# MSB.net
KiCad netlist of a schematic drawn in Altium Designer
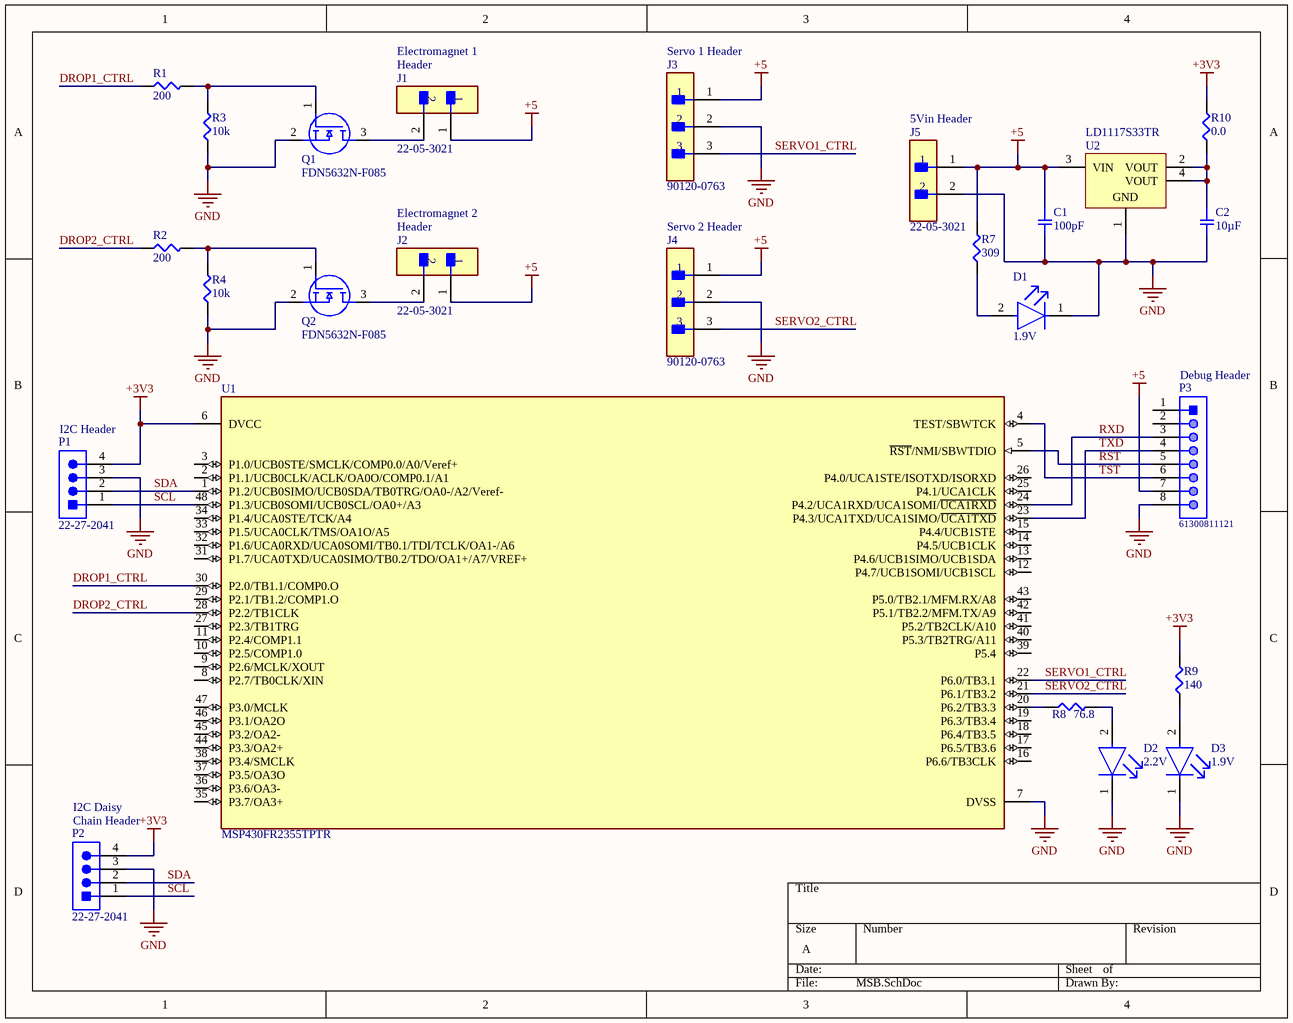
[diagram p0: MSB.SchDoc]

(export (version "E")
  (design (tool "Eeschema 10.0.6"))
  (components
    (comp (ref "C1")
      (value "100pF")
      (footprint "SMD-0805C")
      (description "CAP CER 100PF 50V NP0 0805")
      (fields
        (field (name "MANUFACTURER") "Murata Electronics North America")
        (field (name "TOLERANCE") "±5%")
      )
      (libsource (lib "capacitor_murata_0805") (part "GQM2195C1H101JB01D"))
    )
    (comp (ref "C2")
      (value "10µF")
      (footprint "SMD-0805C")
      (description "CAP CER 10UF 10V X7R 0805")
      (fields
        (field (name "MANUFACTURER") "Murata Electronics North America")
        (field (name "TOLERANCE") "±10%")
      )
      (libsource (lib "capacitor_murata_0805") (part "GCJ21BR71A106KE01L"))
    )
    (comp (ref "D1")
      (value "1.9V")
      (footprint "FP-150080SS75000-MFG")
      (description "LED RED CLEAR 0805 SMD, 150080SS75000")
      (fields
        (field (name "MANUFACTURER") "Wurth Elektronik")
        (field (name "MANUFACTURER PART NUMBER") "150080SS75000")
      )
      (libsource (lib "Altium Content Vault") (part "8706943c75ba83719d021d2fdc84c58"))
    )
    (comp (ref "D2")
      (value "2.2V")
      (footprint "FP-LTST-C171GKT-MFG")
      (description "LED GREEN CLEAR CHIP SMD, LTST-C171GKT")
      (fields (field (name "MANUFACTURER") "Vishay") (field (name "MANUFACTURER PART NUMBER") "LTST-C171GKT"))
      (libsource (lib "Altium Content Vault") (part "8706943c75ba83719d021d2fdc84c58"))
    )
    (comp (ref "D3")
      (value "1.9V")
      (footprint "FP-150080SS75000-MFG")
      (description "LED RED CLEAR 0805 SMD, 150080SS75000")
      (fields
        (field (name "MANUFACTURER") "Wurth Elektronik")
        (field (name "MANUFACTURER PART NUMBER") "150080SS75000")
      )
      (libsource (lib "Altium Content Vault") (part "8706943c75ba83719d021d2fdc84c58"))
    )
    (comp (ref "J1")
      (value "22-05-3021")
      (footprint "FP-22-05-3021-MFG")
      (description "CONN HEADER R/A 2POS 2.54MM")
      (fields (field (name "MANUFACTURER") "Molex"))
      (libsource (lib "Altium Content Vault") (part "3bc925449376181038e59eaffc5286c"))
    )
    (comp (ref "J2")
      (value "22-05-3021")
      (footprint "FP-22-05-3021-MFG")
      (description "CONN HEADER R/A 2POS 2.54MM")
      (fields (field (name "MANUFACTURER") "Molex"))
      (libsource (lib "Altium Content Vault") (part "3bc925449376181038e59eaffc5286c"))
    )
    (comp (ref "J3")
      (value "90120-0763")
      (footprint "FP-90120-0763-MFG")
      (description "CONN HEADER VERT 3POS 2.54MM")
      (fields (field (name "MANUFACTURER") "Molex"))
      (libsource (lib "Altium Content Vault") (part "0d3f023dd272f625e17a2be33dea85f"))
    )
    (comp (ref "J4")
      (value "90120-0763")
      (footprint "FP-90120-0763-MFG")
      (description "CONN HEADER VERT 3POS 2.54MM")
      (fields (field (name "MANUFACTURER") "Molex"))
      (libsource (lib "Altium Content Vault") (part "0d3f023dd272f625e17a2be33dea85f"))
    )
    (comp (ref "J5")
      (value "22-05-3021")
      (footprint "FP-22-05-3021-MFG")
      (description "CONN HEADER R/A 2POS 2.54MM")
      (fields (field (name "MANUFACTURER") "Molex"))
      (libsource (lib "") (part "3bc925449376181038e59eaffc5286c_1"))
    )
    (comp (ref "P1")
      (value "22-27-2041")
      (footprint "MOLX-22-27-2041_V")
      (description "Male Header, Pitch 2.54 mm, 1 x 4 Position, Height 11.7 mm, Tail Length 3.56 mm, RoHS, Bulk")
      (fields (field (name "MANUFACTURER") "Molex"))
      (libsource (lib "Altium Content Vault") (part "CN-1P-M-R4"))
    )
    (comp (ref "P2")
      (value "22-27-2041")
      (footprint "MOLX-22-27-2041_V")
      (description "Male Header, Pitch 2.54 mm, 1 x 4 Position, Height 11.7 mm, Tail Length 3.56 mm, RoHS, Bulk")
      (fields (field (name "MANUFACTURER") "Molex"))
      (libsource (lib "Altium Content Vault") (part "CN-1P-M-R4"))
    )
    (comp (ref "P3")
      (value "61300811121")
      (footprint "61300811121")
      (description "THT Vertical Pin Header WR-PHD, Pitch 2.54 mm, Single Row, 8 pins")
      (fields (field (name "MANUFACTURER") "Wurth Elektronik"))
      (libsource (lib "Altium Content Vault") (part "WE-CN-1P-M-R8"))
    )
    (comp (ref "Q1")
      (value "FDN5632N-F085")
      (footprint "SOT95P237X122-3N")
      (description "MOSFET Trans MOS N-Ch 60V 1.7A")
      (fields (field (name "MANUFACTURER") "Onsemi"))
      (libsource (lib "FDN5632N-F085") (part "FDN5632N-F085"))
    )
    (comp (ref "Q2")
      (value "FDN5632N-F085")
      (footprint "SOT95P237X122-3N")
      (description "MOSFET Trans MOS N-Ch 60V 1.7A")
      (fields (field (name "MANUFACTURER") "Onsemi"))
      (libsource (lib "FDN5632N-F085") (part "FDN5632N-F085"))
    )
    (comp (ref "R1")
      (value "200")
      (footprint "SMD-0805-RES")
      (description "RES SMD 200 OHM 0.5% 1/4W 0805")
      (fields
        (field (name "MANUFACTURER") "Panasonic Electronic Components")
        (field (name "TOLERANCE") "±0.5%")
      )
      (libsource (lib "Panasonic_resistor_0805") (part "ERJ-PB6D2000V"))
    )
    (comp (ref "R2")
      (value "200")
      (footprint "SMD-0805-RES")
      (description "RES SMD 200 OHM 0.5% 1/4W 0805")
      (fields
        (field (name "MANUFACTURER") "Panasonic Electronic Components")
        (field (name "TOLERANCE") "±0.5%")
      )
      (libsource (lib "Panasonic_resistor_0805") (part "ERJ-PB6D2000V"))
    )
    (comp (ref "R3")
      (value "10k")
      (footprint "SMD-0805-RES")
      (description "RES SMD 10K OHM 1% 1/8W 0805")
      (fields
        (field (name "MANUFACTURER") "Panasonic Electronic Components")
        (field (name "TOLERANCE") "±1%")
      )
      (libsource (lib "Panasonic_resistor_0805") (part "ERJ-6ENF1002V"))
    )
    (comp (ref "R4")
      (value "10k")
      (footprint "SMD-0805-RES")
      (description "RES SMD 10K OHM 1% 1/8W 0805")
      (fields
        (field (name "MANUFACTURER") "Panasonic Electronic Components")
        (field (name "TOLERANCE") "±1%")
      )
      (libsource (lib "Panasonic_resistor_0805") (part "ERJ-6ENF1002V"))
    )
    (comp (ref "R7")
      (value "309")
      (footprint "SMD-0805-RES")
      (description "RES SMD 309 OHM 1% 1/8W 0805")
      (fields
        (field (name "MANUFACTURER") "Panasonic Electronic Components")
        (field (name "TOLERANCE") "±1%")
      )
      (libsource (lib "Panasonic_resistor_0805") (part "ERJ-6ENF3090V"))
    )
    (comp (ref "R8")
      (value "76.8")
      (footprint "SMD-0805-RES")
      (description "RES SMD 76.8 OHM 1% 1/8W 0805")
      (fields
        (field (name "MANUFACTURER") "Panasonic Electronic Components")
        (field (name "TOLERANCE") "±1%")
      )
      (libsource (lib "Panasonic_resistor_0805") (part "ERJ-6ENF76R8V"))
    )
    (comp (ref "R9")
      (value "140")
      (footprint "SMD-0805-RES")
      (description "RES SMD 140 OHM 1% 1/8W 0805")
      (fields
        (field (name "MANUFACTURER") "Panasonic Electronic Components")
        (field (name "TOLERANCE") "±1%")
      )
      (libsource (lib "Panasonic_resistor_0805") (part "ERJ-6ENF1400V"))
    )
    (comp (ref "R10")
      (value "0.0")
      (footprint "SMD-0805-RES")
      (description "RES SMD 0.0 OHM JUMPER 1/8W 0805")
      (fields
        (field (name "MANUFACTURER") "Panasonic Electronic Components")
        (field (name "TOLERANCE") "Jumper")
      )
      (libsource (lib "Panasonic_resistor_0805") (part "ERJ-6GEY0R00V"))
    )
    (comp (ref "U1")
      (value "MSP430FR2355TPTR")
      (footprint "FP-PT0048A-MFG")
      (description "IC MCU 16BIT 32KB FRAM 48LQFP")
      (fields (field (name "MANUFACTURER") "Texas Instruments"))
      (libsource (lib "Altium Content Vault") (part "bd983ca6877cdd146f198514b3acb3b"))
    )
    (comp (ref "U2")
      (value "LD1117S33TR")
      (footprint "SOT-223_L")
      (description "Fixed Low Drop Positive Voltage Regulator, 3.3V, 4-Pin SOT-223, Tape and Reel")
      (fields (field (name "MANUFACTURER") "Onsemi"))
      (libsource (lib "Altium Content Vault") (part "PM-REG-LD1117-SOT4"))
    )
  )
  (nets
    (net (code "1") (name "+3V3") (class "Default")
      (node (ref "P1") (pin "4") (pinfunction "4_4") (pintype "passive"))
      (node (ref "P2") (pin "4") (pinfunction "4_4") (pintype "passive"))
      (node (ref "R10") (pin "2") (pinfunction "2_2") (pintype "passive"))
      (node (ref "R9") (pin "2") (pinfunction "2_2") (pintype "passive"))
      (node (ref "U1") (pin "6") (pinfunction "DVCC_6") (pintype "power_in"))
    )
    (net (code "2") (name "+5") (class "Default")
      (node (ref "C1") (pin "1") (pinfunction "1_1") (pintype "passive"))
      (node (ref "J1") (pin "1") (pinfunction "1_1") (pintype "passive"))
      (node (ref "J2") (pin "1") (pinfunction "1_1") (pintype "passive"))
      (node (ref "J3") (pin "1") (pinfunction "1_1") (pintype "passive"))
      (node (ref "J4") (pin "1") (pinfunction "1_1") (pintype "passive"))
      (node (ref "J5") (pin "1") (pinfunction "1_1") (pintype "passive"))
      (node (ref "P3") (pin "7") (pinfunction "7_7") (pintype "passive"))
      (node (ref "R7") (pin "2") (pinfunction "2_2") (pintype "passive"))
      (node (ref "U2") (pin "3") (pinfunction "VIN_3") (pintype "power_in"))
    )
    (net (code "3") (name "/DROP1_CTRL") (class "Default")
      (node (ref "R1") (pin "1") (pinfunction "1_1") (pintype "passive"))
      (node (ref "U1") (pin "30") (pinfunction "P2.0/TB1.1/COMP0.O_30") (pintype "bidirectional"))
    )
    (net (code "4") (name "/DROP2_CTRL") (class "Default")
      (node (ref "R2") (pin "1") (pinfunction "1_1") (pintype "passive"))
      (node (ref "U1") (pin "28") (pinfunction "P2.2/TB1CLK_28") (pintype "bidirectional"))
    )
    (net (code "5") (name "/RST") (class "Default")
      (node (ref "P3") (pin "5") (pinfunction "5_5") (pintype "passive"))
      (node (ref "U1") (pin "5") (pinfunction "~{RST}/NMI/SBWTDIO_5") (pintype "input"))
    )
    (net (code "6") (name "/RXD") (class "Default")
      (node (ref "P3") (pin "3") (pinfunction "3_3") (pintype "passive"))
      (node (ref "U1") (pin "24") (pinfunction "P4.2/UCA1RXD/UCA1SOMI/~{UCA1RXD}_24") (pintype "bidirectional"))
    )
    (net (code "7") (name "/SCL") (class "Default")
      (node (ref "P1") (pin "1") (pinfunction "1_1") (pintype "passive"))
      (node (ref "P2") (pin "1") (pinfunction "1_1") (pintype "passive"))
      (node (ref "U1") (pin "48") (pinfunction "P1.3/UCB0SOMI/UCB0SCL/OA0+/A3_48") (pintype "bidirectional"))
    )
    (net (code "8") (name "/SDA") (class "Default")
      (node (ref "P1") (pin "2") (pinfunction "2_2") (pintype "passive"))
      (node (ref "P2") (pin "2") (pinfunction "2_2") (pintype "passive"))
      (node (ref "U1") (pin "1") (pinfunction "P1.2/UCB0SIMO/UCB0SDA/TB0TRG/OA0-/A2/Veref-_1") (pintype "bidirectional"))
    )
    (net (code "9") (name "/SERVO1_CTRL") (class "Default")
      (node (ref "J3") (pin "3") (pinfunction "3_3") (pintype "passive"))
      (node (ref "U1") (pin "22") (pinfunction "P6.0/TB3.1_22") (pintype "bidirectional"))
    )
    (net (code "10") (name "/SERVO2_CTRL") (class "Default")
      (node (ref "J4") (pin "3") (pinfunction "3_3") (pintype "passive"))
      (node (ref "U1") (pin "21") (pinfunction "P6.1/TB3.2_21") (pintype "bidirectional"))
    )
    (net (code "11") (name "/TST") (class "Default")
      (node (ref "P3") (pin "6") (pinfunction "6_6") (pintype "passive"))
      (node (ref "U1") (pin "4") (pinfunction "TEST/SBWTCK_4") (pintype "bidirectional"))
    )
    (net (code "12") (name "/TXD") (class "Default")
      (node (ref "P3") (pin "4") (pinfunction "4_4") (pintype "passive"))
      (node (ref "U1") (pin "23") (pinfunction "P4.3/UCA1TXD/UCA1SIMO/~{UCA1TXD}_23") (pintype "bidirectional"))
    )
    (net (code "13") (name "GND") (class "Default")
      (node (ref "C1") (pin "2") (pinfunction "2_2") (pintype "passive"))
      (node (ref "C2") (pin "2") (pinfunction "2_2") (pintype "passive"))
      (node (ref "D1") (pin "1") (pinfunction "C_1") (pintype "passive"))
      (node (ref "D2") (pin "1") (pinfunction "C_1") (pintype "passive"))
      (node (ref "D3") (pin "1") (pinfunction "C_1") (pintype "passive"))
      (node (ref "J3") (pin "2") (pinfunction "2_2") (pintype "passive"))
      (node (ref "J4") (pin "2") (pinfunction "2_2") (pintype "passive"))
      (node (ref "J5") (pin "2") (pinfunction "2_2") (pintype "passive"))
      (node (ref "P1") (pin "3") (pinfunction "3_3") (pintype "passive"))
      (node (ref "P2") (pin "3") (pinfunction "3_3") (pintype "passive"))
      (node (ref "P3") (pin "8") (pinfunction "8_8") (pintype "passive"))
      (node (ref "Q1") (pin "2") (pinfunction "S_2") (pintype "passive"))
      (node (ref "Q2") (pin "2") (pinfunction "S_2") (pintype "passive"))
      (node (ref "R3") (pin "1") (pinfunction "1_1") (pintype "passive"))
      (node (ref "R4") (pin "1") (pinfunction "1_1") (pintype "passive"))
      (node (ref "U1") (pin "7") (pinfunction "DVSS_7") (pintype "power_in"))
      (node (ref "U2") (pin "1") (pinfunction "GND_1") (pintype "power_in"))
    )
    (net (code "14") (name "Net-(C2-Pad1)") (class "Default")
      (node (ref "C2") (pin "1") (pinfunction "1_1") (pintype "passive"))
      (node (ref "R10") (pin "1") (pinfunction "1_1") (pintype "passive"))
      (node (ref "U2") (pin "2") (pinfunction "VOUT_2") (pintype "power_in"))
      (node (ref "U2") (pin "4") (pinfunction "VOUT_4") (pintype "power_in"))
    )
    (net (code "15") (name "Net-(D1-A)") (class "Default")
      (node (ref "D1") (pin "2") (pinfunction "A_2") (pintype "passive"))
      (node (ref "R7") (pin "1") (pinfunction "1_1") (pintype "passive"))
    )
    (net (code "16") (name "Net-(D2-A)") (class "Default")
      (node (ref "D2") (pin "2") (pinfunction "A_2") (pintype "passive"))
      (node (ref "R8") (pin "2") (pinfunction "2_2") (pintype "passive"))
    )
    (net (code "17") (name "Net-(D3-A)") (class "Default")
      (node (ref "D3") (pin "2") (pinfunction "A_2") (pintype "passive"))
      (node (ref "R9") (pin "1") (pinfunction "1_1") (pintype "passive"))
    )
    (net (code "18") (name "Net-(Q1-D)") (class "Default")
      (node (ref "J1") (pin "2") (pinfunction "2_2") (pintype "passive"))
      (node (ref "Q1") (pin "3") (pinfunction "D_3") (pintype "passive"))
    )
    (net (code "19") (name "Net-(Q1-G)") (class "Default")
      (node (ref "Q1") (pin "1") (pinfunction "G_1") (pintype "passive"))
      (node (ref "R1") (pin "2") (pinfunction "2_2") (pintype "passive"))
      (node (ref "R3") (pin "2") (pinfunction "2_2") (pintype "passive"))
    )
    (net (code "20") (name "Net-(Q2-D)") (class "Default")
      (node (ref "J2") (pin "2") (pinfunction "2_2") (pintype "passive"))
      (node (ref "Q2") (pin "3") (pinfunction "D_3") (pintype "passive"))
    )
    (net (code "21") (name "Net-(Q2-G)") (class "Default")
      (node (ref "Q2") (pin "1") (pinfunction "G_1") (pintype "passive"))
      (node (ref "R2") (pin "2") (pinfunction "2_2") (pintype "passive"))
      (node (ref "R4") (pin "2") (pinfunction "2_2") (pintype "passive"))
    )
    (net (code "22") (name "Net-(U1-P6.2{slash}TB3.3)") (class "Default")
      (node (ref "R8") (pin "1") (pinfunction "1_1") (pintype "passive"))
      (node (ref "U1") (pin "20") (pinfunction "P6.2/TB3.3_20") (pintype "bidirectional"))
    )
    (net (code "23") (name "unconnected-(P3-Pad1)") (class "Default")
      (node (ref "P3") (pin "1") (pinfunction "1_1") (pintype "passive"))
    )
    (net (code "24") (name "unconnected-(P3-Pad2)") (class "Default")
      (node (ref "P3") (pin "2") (pinfunction "2_2") (pintype "passive"))
    )
    (net (code "25") (name "unconnected-(U1-P1.0{slash}UCB0STE{slash}SMCLK{slash}COMP0.0{slash}A0{slash}Veref+-Pad3)") (class "Default")
      (node (ref "U1") (pin "3") (pinfunction "P1.0/UCB0STE/SMCLK/COMP0.0/A0/Veref+_3") (pintype "bidirectional"))
    )
    (net (code "26") (name "unconnected-(U1-P1.1{slash}UCB0CLK{slash}ACLK{slash}OA0O{slash}COMP0.1{slash}A1-Pad2)") (class "Default")
      (node (ref "U1") (pin "2") (pinfunction "P1.1/UCB0CLK/ACLK/OA0O/COMP0.1/A1_2") (pintype "bidirectional"))
    )
    (net (code "27") (name "unconnected-(U1-P1.4{slash}UCA0STE{slash}TCK{slash}A4-Pad34)") (class "Default")
      (node (ref "U1") (pin "34") (pinfunction "P1.4/UCA0STE/TCK/A4_34") (pintype "bidirectional"))
    )
    (net (code "28") (name "unconnected-(U1-P1.5{slash}UCA0CLK{slash}TMS{slash}OA1O{slash}A5-Pad33)") (class "Default")
      (node (ref "U1") (pin "33") (pinfunction "P1.5/UCA0CLK/TMS/OA1O/A5_33") (pintype "bidirectional"))
    )
    (net (code "29") (name "unconnected-(U1-P1.6{slash}UCA0RXD{slash}UCA0SOMI{slash}TB0.1{slash}TDI{slash}TCLK{slash}OA1-{slash}A6-Pad32)") (class "Default")
      (node (ref "U1") (pin "32") (pinfunction "P1.6/UCA0RXD/UCA0SOMI/TB0.1/TDI/TCLK/OA1-/A6_32") (pintype "bidirectional"))
    )
    (net (code "30") (name "unconnected-(U1-P1.7{slash}UCA0TXD{slash}UCA0SIMO{slash}TB0.2{slash}TDO{slash}OA1+{slash}A7{slash}VREF+-Pad31)") (class "Default")
      (node (ref "U1") (pin "31") (pinfunction "P1.7/UCA0TXD/UCA0SIMO/TB0.2/TDO/OA1+/A7/VREF+_31") (pintype "bidirectional"))
    )
    (net (code "31") (name "unconnected-(U1-P2.1{slash}TB1.2{slash}COMP1.O-Pad29)") (class "Default")
      (node (ref "U1") (pin "29") (pinfunction "P2.1/TB1.2/COMP1.O_29") (pintype "bidirectional"))
    )
    (net (code "32") (name "unconnected-(U1-P2.3{slash}TB1TRG-Pad27)") (class "Default")
      (node (ref "U1") (pin "27") (pinfunction "P2.3/TB1TRG_27") (pintype "bidirectional"))
    )
    (net (code "33") (name "unconnected-(U1-P2.4{slash}COMP1.1-Pad11)") (class "Default")
      (node (ref "U1") (pin "11") (pinfunction "P2.4/COMP1.1_11") (pintype "bidirectional"))
    )
    (net (code "34") (name "unconnected-(U1-P2.5{slash}COMP1.0-Pad10)") (class "Default")
      (node (ref "U1") (pin "10") (pinfunction "P2.5/COMP1.0_10") (pintype "bidirectional"))
    )
    (net (code "35") (name "unconnected-(U1-P2.6{slash}MCLK{slash}XOUT-Pad9)") (class "Default")
      (node (ref "U1") (pin "9") (pinfunction "P2.6/MCLK/XOUT_9") (pintype "bidirectional"))
    )
    (net (code "36") (name "unconnected-(U1-P2.7{slash}TB0CLK{slash}XIN-Pad8)") (class "Default")
      (node (ref "U1") (pin "8") (pinfunction "P2.7/TB0CLK/XIN_8") (pintype "bidirectional"))
    )
    (net (code "37") (name "unconnected-(U1-P3.0{slash}MCLK-Pad47)") (class "Default")
      (node (ref "U1") (pin "47") (pinfunction "P3.0/MCLK_47") (pintype "bidirectional"))
    )
    (net (code "38") (name "unconnected-(U1-P3.1{slash}OA2O-Pad46)") (class "Default")
      (node (ref "U1") (pin "46") (pinfunction "P3.1/OA2O_46") (pintype "bidirectional"))
    )
    (net (code "39") (name "unconnected-(U1-P3.2{slash}OA2--Pad45)") (class "Default")
      (node (ref "U1") (pin "45") (pinfunction "P3.2/OA2-_45") (pintype "bidirectional"))
    )
    (net (code "40") (name "unconnected-(U1-P3.3{slash}OA2+-Pad44)") (class "Default")
      (node (ref "U1") (pin "44") (pinfunction "P3.3/OA2+_44") (pintype "bidirectional"))
    )
    (net (code "41") (name "unconnected-(U1-P3.4{slash}SMCLK-Pad38)") (class "Default")
      (node (ref "U1") (pin "38") (pinfunction "P3.4/SMCLK_38") (pintype "bidirectional"))
    )
    (net (code "42") (name "unconnected-(U1-P3.5{slash}OA3O-Pad37)") (class "Default")
      (node (ref "U1") (pin "37") (pinfunction "P3.5/OA3O_37") (pintype "bidirectional"))
    )
    (net (code "43") (name "unconnected-(U1-P3.6{slash}OA3--Pad36)") (class "Default")
      (node (ref "U1") (pin "36") (pinfunction "P3.6/OA3-_36") (pintype "bidirectional"))
    )
    (net (code "44") (name "unconnected-(U1-P3.7{slash}OA3+-Pad35)") (class "Default")
      (node (ref "U1") (pin "35") (pinfunction "P3.7/OA3+_35") (pintype "bidirectional"))
    )
    (net (code "45") (name "unconnected-(U1-P4.0{slash}UCA1STE{slash}ISOTXD{slash}ISORXD-Pad26)") (class "Default")
      (node (ref "U1") (pin "26") (pinfunction "P4.0/UCA1STE/ISOTXD/ISORXD_26") (pintype "bidirectional"))
    )
    (net (code "46") (name "unconnected-(U1-P4.1{slash}UCA1CLK-Pad25)") (class "Default")
      (node (ref "U1") (pin "25") (pinfunction "P4.1/UCA1CLK_25") (pintype "bidirectional"))
    )
    (net (code "47") (name "unconnected-(U1-P4.4{slash}UCB1STE-Pad15)") (class "Default")
      (node (ref "U1") (pin "15") (pinfunction "P4.4/UCB1STE_15") (pintype "bidirectional"))
    )
    (net (code "48") (name "unconnected-(U1-P4.5{slash}UCB1CLK-Pad14)") (class "Default")
      (node (ref "U1") (pin "14") (pinfunction "P4.5/UCB1CLK_14") (pintype "bidirectional"))
    )
    (net (code "49") (name "unconnected-(U1-P4.6{slash}UCB1SIMO{slash}UCB1SDA-Pad13)") (class "Default")
      (node (ref "U1") (pin "13") (pinfunction "P4.6/UCB1SIMO/UCB1SDA_13") (pintype "bidirectional"))
    )
    (net (code "50") (name "unconnected-(U1-P4.7{slash}UCB1SOMI{slash}UCB1SCL-Pad12)") (class "Default")
      (node (ref "U1") (pin "12") (pinfunction "P4.7/UCB1SOMI/UCB1SCL_12") (pintype "bidirectional"))
    )
    (net (code "51") (name "unconnected-(U1-P5.0{slash}TB2.1{slash}MFM.RX{slash}A8-Pad43)") (class "Default")
      (node (ref "U1") (pin "43") (pinfunction "P5.0/TB2.1/MFM.RX/A8_43") (pintype "bidirectional"))
    )
    (net (code "52") (name "unconnected-(U1-P5.1{slash}TB2.2{slash}MFM.TX{slash}A9-Pad42)") (class "Default")
      (node (ref "U1") (pin "42") (pinfunction "P5.1/TB2.2/MFM.TX/A9_42") (pintype "bidirectional"))
    )
    (net (code "53") (name "unconnected-(U1-P5.2{slash}TB2CLK{slash}A10-Pad41)") (class "Default")
      (node (ref "U1") (pin "41") (pinfunction "P5.2/TB2CLK/A10_41") (pintype "bidirectional"))
    )
    (net (code "54") (name "unconnected-(U1-P5.3{slash}TB2TRG{slash}A11-Pad40)") (class "Default")
      (node (ref "U1") (pin "40") (pinfunction "P5.3/TB2TRG/A11_40") (pintype "bidirectional"))
    )
    (net (code "55") (name "unconnected-(U1-P5.4-Pad39)") (class "Default")
      (node (ref "U1") (pin "39") (pinfunction "P5.4_39") (pintype "bidirectional"))
    )
    (net (code "56") (name "unconnected-(U1-P6.3{slash}TB3.4-Pad19)") (class "Default")
      (node (ref "U1") (pin "19") (pinfunction "P6.3/TB3.4_19") (pintype "bidirectional"))
    )
    (net (code "57") (name "unconnected-(U1-P6.4{slash}TB3.5-Pad18)") (class "Default")
      (node (ref "U1") (pin "18") (pinfunction "P6.4/TB3.5_18") (pintype "bidirectional"))
    )
    (net (code "58") (name "unconnected-(U1-P6.5{slash}TB3.6-Pad17)") (class "Default")
      (node (ref "U1") (pin "17") (pinfunction "P6.5/TB3.6_17") (pintype "bidirectional"))
    )
    (net (code "59") (name "unconnected-(U1-P6.6{slash}TB3CLK-Pad16)") (class "Default")
      (node (ref "U1") (pin "16") (pinfunction "P6.6/TB3CLK_16") (pintype "bidirectional"))
    )
  )
)
